# MainBoard_Light.net
KiCad netlist of a schematic drawn in Altium Designer
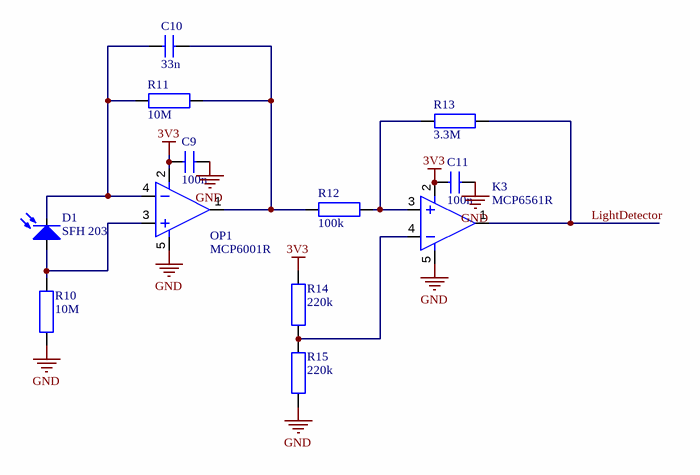
[diagram p0: MainBoard_Light.SchDoc]

(export (version "E")
  (design (tool "Eeschema 10.0.6"))
  (components
    (comp (ref "C9")
      (value "100n")
      (footprint "0805_C")
      (description "Normaler Kondensator")
      (libsource (lib "MainBoard") (part "C?"))
    )
    (comp (ref "C10")
      (value "33n")
      (footprint "0805_C")
      (description "Normaler Kondensator")
      (libsource (lib "MainBoard") (part "C?"))
    )
    (comp (ref "C11")
      (value "100n")
      (footprint "0805_C")
      (description "Normaler Kondensator")
      (libsource (lib "MainBoard") (part "C?"))
    )
    (comp (ref "D1")
      (value "SFH 203")
      (footprint "LED_THT_5mm_RM_2.54mm")
      (description "Photo_Diode_1A_2K")
      (libsource (lib "Sch_Lib") (part "Photo_Diode_1A_2K"))
    )
    (comp (ref "K3") (value "MCP6561R") (footprint "SOT23-5") (libsource (lib "") (part "OPAMP_1")))
    (comp (ref "OP1") (value "MCP6001R") (footprint "SOT23-5") (libsource (lib "MainBoard") (part "OPAMP")))
    (comp (ref "R10")
      (value "10M")
      (footprint "0805_R")
      (description "Normaler Widerstand")
      (libsource (lib "MainBoard") (part "R?"))
    )
    (comp (ref "R11")
      (value "10M")
      (footprint "0805_R")
      (description "Normaler Widerstand")
      (libsource (lib "MainBoard") (part "R?"))
    )
    (comp (ref "R12")
      (value "100k")
      (footprint "0805_R")
      (description "Normaler Widerstand")
      (libsource (lib "MainBoard") (part "R?"))
    )
    (comp (ref "R13")
      (value "3.3M")
      (footprint "0805_R")
      (description "Normaler Widerstand")
      (libsource (lib "MainBoard") (part "R?"))
    )
    (comp (ref "R14")
      (value "220k")
      (footprint "0805_R")
      (description "Normaler Widerstand")
      (libsource (lib "MainBoard") (part "R?"))
    )
    (comp (ref "R15")
      (value "220k")
      (footprint "0805_R")
      (description "Normaler Widerstand")
      (libsource (lib "MainBoard") (part "R?"))
    )
  )
  (nets
    (net (code "1") (name "/LightDetector") (class "Default")
      (node (ref "K3") (pin "1") (pinfunction "1_1") (pintype "passive"))
      (node (ref "R13") (pin "1") (pintype "passive"))
    )
    (net (code "2") (name "3V3") (class "Default")
      (node (ref "C11") (pin "1") (pinfunction "1_1") (pintype "passive"))
      (node (ref "C9") (pin "1") (pinfunction "1_1") (pintype "passive"))
      (node (ref "K3") (pin "2") (pinfunction "2_2") (pintype "passive"))
      (node (ref "OP1") (pin "2") (pinfunction "2_2") (pintype "passive"))
      (node (ref "R14") (pin "1") (pintype "passive"))
    )
    (net (code "3") (name "GND") (class "Default")
      (node (ref "C11") (pin "2") (pinfunction "2_2") (pintype "passive"))
      (node (ref "C9") (pin "2") (pinfunction "2_2") (pintype "passive"))
      (node (ref "K3") (pin "5") (pinfunction "5_5") (pintype "passive"))
      (node (ref "OP1") (pin "5") (pinfunction "5_5") (pintype "passive"))
      (node (ref "R10") (pin "2") (pintype "passive"))
      (node (ref "R15") (pin "2") (pintype "passive"))
    )
    (net (code "4") (name "Net-(C10-Pad2)") (class "Default")
      (node (ref "C10") (pin "2") (pinfunction "2_2") (pintype "passive"))
      (node (ref "OP1") (pin "1") (pinfunction "1_1") (pintype "passive"))
      (node (ref "R11") (pin "1") (pintype "passive"))
      (node (ref "R12") (pin "2") (pintype "passive"))
    )
    (net (code "5") (name "Net-(D1-A)") (class "Default")
      (node (ref "D1") (pin "1") (pinfunction "A_1") (pintype "passive"))
      (node (ref "OP1") (pin "3") (pinfunction "3_3") (pintype "passive"))
      (node (ref "R10") (pin "1") (pintype "passive"))
    )
    (net (code "6") (name "Net-(D1-K)") (class "Default")
      (node (ref "C10") (pin "1") (pinfunction "1_1") (pintype "passive"))
      (node (ref "D1") (pin "2") (pinfunction "K_2") (pintype "passive"))
      (node (ref "OP1") (pin "4") (pinfunction "4_4") (pintype "passive"))
      (node (ref "R11") (pin "2") (pintype "passive"))
    )
    (net (code "7") (name "Net-(K3-Pad3)") (class "Default")
      (node (ref "K3") (pin "3") (pinfunction "3_3") (pintype "passive"))
      (node (ref "R12") (pin "1") (pintype "passive"))
      (node (ref "R13") (pin "2") (pintype "passive"))
    )
    (net (code "8") (name "Net-(K3-Pad4)") (class "Default")
      (node (ref "K3") (pin "4") (pinfunction "4_4") (pintype "passive"))
      (node (ref "R14") (pin "2") (pintype "passive"))
      (node (ref "R15") (pin "1") (pintype "passive"))
    )
  )
)
